# Open_Playback_Recorder_Top.net
KiCad netlist of a schematic drawn in EAGLE
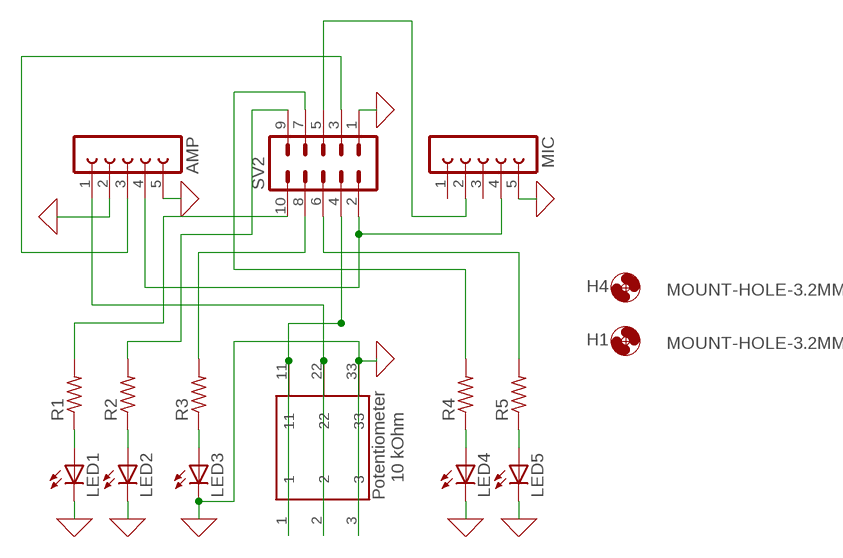
[diagram p0: schematic, sheet 1]

(export (version "E")
  (design (tool "Eeschema 10.0.6"))
  (components
    (comp (ref "AMP")
      (value "FE05-1")
      (footprint "eagle-import:FE05-1")
      (libsource (lib "eagle-import") (part "FE05-1"))
    )
    (comp (ref "H1")
      (value "MOUNT-HOLE-3.2MM")
      (footprint "eagle-import:HOLE-3.2MM")
      (libsource (lib "eagle-import") (part "MOUNT-HOLE-3.2MM"))
    )
    (comp (ref "H4")
      (value "MOUNT-HOLE-3.2MM")
      (footprint "eagle-import:HOLE-3.2MM")
      (libsource (lib "eagle-import") (part "MOUNT-HOLE-3.2MM"))
    )
    (comp (ref "LED1")
      (value "LED5MM")
      (footprint "eagle-import:LED5MM")
      (libsource (lib "eagle-import") (part "LED5MM"))
    )
    (comp (ref "LED2")
      (value "LED5MM")
      (footprint "eagle-import:LED5MM")
      (libsource (lib "eagle-import") (part "LED5MM"))
    )
    (comp (ref "LED3")
      (value "LED5MM")
      (footprint "eagle-import:LED5MM")
      (libsource (lib "eagle-import") (part "LED5MM"))
    )
    (comp (ref "LED4")
      (value "LED5MM")
      (footprint "eagle-import:LED5MM")
      (libsource (lib "eagle-import") (part "LED5MM"))
    )
    (comp (ref "LED5")
      (value "LED5MM")
      (footprint "eagle-import:LED5MM")
      (libsource (lib "eagle-import") (part "LED5MM"))
    )
    (comp (ref "MIC")
      (value "FE05-1")
      (footprint "eagle-import:FE05-1")
      (libsource (lib "eagle-import") (part "FE05-1"))
    )
    (comp (ref "R1")
      (value "RESISTOR-US-0206/80206/8")
      (footprint "eagle-import:RESISTOR_0206_8")
      (libsource (lib "eagle-import") (part "RESISTOR-US-0206/80206/8"))
    )
    (comp (ref "R2")
      (value "RESISTOR-US-0206/80206/8")
      (footprint "eagle-import:RESISTOR_0206_8")
      (libsource (lib "eagle-import") (part "RESISTOR-US-0206/80206/8"))
    )
    (comp (ref "R3")
      (value "RESISTOR-US-0206/80206/8")
      (footprint "eagle-import:RESISTOR_0206_8")
      (libsource (lib "eagle-import") (part "RESISTOR-US-0206/80206/8"))
    )
    (comp (ref "R4")
      (value "RESISTOR-US-0206/80206/8")
      (footprint "eagle-import:RESISTOR_0206_8")
      (libsource (lib "eagle-import") (part "RESISTOR-US-0206/80206/8"))
    )
    (comp (ref "R5")
      (value "RESISTOR-US-0206/80206/8")
      (footprint "eagle-import:RESISTOR_0206_8")
      (libsource (lib "eagle-import") (part "RESISTOR-US-0206/80206/8"))
    )
    (comp (ref "SV2")
      (value "MA05-2")
      (footprint "eagle-import:MA05-2")
      (libsource (lib "eagle-import") (part "MA05-2"))
    )
    (comp (ref "U$2")
      (value "POTENTIOMETER")
      (footprint "eagle-import:POTENTIOMETER")
      (libsource (lib "eagle-import") (part "POTENTIOMETER"))
    )
  )
  (nets
    (net (code "1") (name "GND") (class "Default")
      (node (ref "AMP") (pin "2") (pinfunction "2_2") (pintype "passive"))
      (node (ref "AMP") (pin "5") (pinfunction "5_5") (pintype "passive"))
      (node (ref "LED1") (pin "K") (pinfunction "C_K") (pintype "passive"))
      (node (ref "LED2") (pin "K") (pinfunction "C_K") (pintype "passive"))
      (node (ref "LED3") (pin "K") (pinfunction "C_K") (pintype "passive"))
      (node (ref "LED4") (pin "K") (pinfunction "C_K") (pintype "passive"))
      (node (ref "LED5") (pin "K") (pinfunction "C_K") (pintype "passive"))
      (node (ref "MIC") (pin "5") (pinfunction "5_5") (pintype "passive"))
      (node (ref "SV2") (pin "1") (pinfunction "1_1") (pintype "passive"))
      (node (ref "U$2") (pin "3") (pinfunction "3_3") (pintype "bidirectional"))
      (node (ref "U$2") (pin "33") (pinfunction "33_33") (pintype "bidirectional"))
    )
    (net (code "2") (name "Net-(AMP-Pad1)") (class "Default")
      (node (ref "AMP") (pin "1") (pinfunction "1_1") (pintype "passive"))
      (node (ref "U$2") (pin "2") (pinfunction "2_2") (pintype "bidirectional"))
      (node (ref "U$2") (pin "22") (pinfunction "22_22") (pintype "bidirectional"))
    )
    (net (code "3") (name "Net-(AMP-Pad3)") (class "Default")
      (node (ref "AMP") (pin "3") (pinfunction "3_3") (pintype "passive"))
      (node (ref "SV2") (pin "3") (pinfunction "3_3") (pintype "passive"))
    )
    (net (code "4") (name "Net-(AMP-Pad4)") (class "Default")
      (node (ref "AMP") (pin "4") (pinfunction "4_4") (pintype "passive"))
      (node (ref "MIC") (pin "4") (pinfunction "4_4") (pintype "passive"))
      (node (ref "SV2") (pin "2") (pinfunction "2_2") (pintype "passive"))
    )
    (net (code "5") (name "Net-(LED1-PadA)") (class "Default")
      (node (ref "LED1") (pin "A") (pinfunction "A_A") (pintype "passive"))
      (node (ref "R1") (pin "1") (pinfunction "1_1") (pintype "passive"))
    )
    (net (code "6") (name "Net-(LED2-PadA)") (class "Default")
      (node (ref "LED2") (pin "A") (pinfunction "A_A") (pintype "passive"))
      (node (ref "R2") (pin "1") (pinfunction "1_1") (pintype "passive"))
    )
    (net (code "7") (name "Net-(LED3-PadA)") (class "Default")
      (node (ref "LED3") (pin "A") (pinfunction "A_A") (pintype "passive"))
      (node (ref "R3") (pin "1") (pinfunction "1_1") (pintype "passive"))
    )
    (net (code "8") (name "Net-(LED4-PadA)") (class "Default")
      (node (ref "LED4") (pin "A") (pinfunction "A_A") (pintype "passive"))
      (node (ref "R4") (pin "1") (pinfunction "1_1") (pintype "passive"))
    )
    (net (code "9") (name "Net-(LED5-PadA)") (class "Default")
      (node (ref "LED5") (pin "A") (pinfunction "A_A") (pintype "passive"))
      (node (ref "R5") (pin "1") (pinfunction "1_1") (pintype "passive"))
    )
    (net (code "10") (name "Net-(MIC-Pad2)") (class "Default")
      (node (ref "MIC") (pin "2") (pinfunction "2_2") (pintype "passive"))
      (node (ref "SV2") (pin "5") (pinfunction "5_5") (pintype "passive"))
    )
    (net (code "11") (name "Net-(R1-Pad2)") (class "Default")
      (node (ref "R1") (pin "2") (pinfunction "2_2") (pintype "passive"))
      (node (ref "SV2") (pin "10") (pinfunction "10_10") (pintype "passive"))
    )
    (net (code "12") (name "Net-(R2-Pad2)") (class "Default")
      (node (ref "R2") (pin "2") (pinfunction "2_2") (pintype "passive"))
      (node (ref "SV2") (pin "9") (pinfunction "9_9") (pintype "passive"))
    )
    (net (code "13") (name "Net-(R3-Pad2)") (class "Default")
      (node (ref "R3") (pin "2") (pinfunction "2_2") (pintype "passive"))
      (node (ref "SV2") (pin "8") (pinfunction "8_8") (pintype "passive"))
    )
    (net (code "14") (name "Net-(R4-Pad2)") (class "Default")
      (node (ref "R4") (pin "2") (pinfunction "2_2") (pintype "passive"))
      (node (ref "SV2") (pin "7") (pinfunction "7_7") (pintype "passive"))
    )
    (net (code "15") (name "Net-(R5-Pad2)") (class "Default")
      (node (ref "R5") (pin "2") (pinfunction "2_2") (pintype "passive"))
      (node (ref "SV2") (pin "6") (pinfunction "6_6") (pintype "passive"))
    )
    (net (code "16") (name "Net-(SV2-Pad4)") (class "Default")
      (node (ref "SV2") (pin "4") (pinfunction "4_4") (pintype "passive"))
      (node (ref "U$2") (pin "1") (pinfunction "1_1") (pintype "bidirectional"))
      (node (ref "U$2") (pin "11") (pinfunction "11_11") (pintype "bidirectional"))
    )
    (net (code "17") (name "unconnected-(MIC-Pad1)") (class "Default")
      (node (ref "MIC") (pin "1") (pinfunction "1_1") (pintype "passive"))
    )
    (net (code "18") (name "unconnected-(MIC-Pad3)") (class "Default")
      (node (ref "MIC") (pin "3") (pinfunction "3_3") (pintype "passive"))
    )
  )
)
